# Tone_Level.net
KiCad netlist of a schematic drawn in Altium Designer
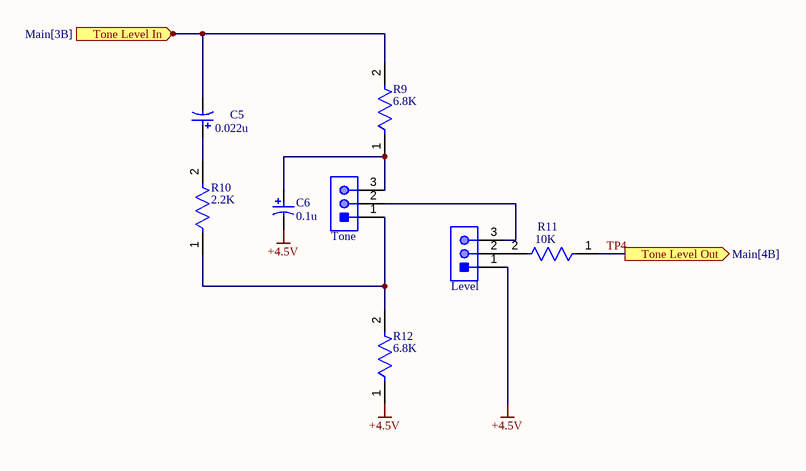
[diagram p0: Tone Level.SchDoc]

(export (version "E")
  (design (tool "Eeschema 10.0.6"))
  (components
    (comp (ref "C5")
      (value "0.022u")
      (footprint "CAPPR55-200-1100X500X1200")
      (description "Aluminum Electrolytic Capacitor, 22 uF, +/- 20%, 50 V, -40 to 85 degC, 2-Pin THD, RoHS, Bulk")
      (fields (field (name "VOLTAGE") "50V") (field (name "MANUFACTURER") "Panasonic"))
      (libsource (lib "Altium Content Vault") (part "CAP-P-2"))
    )
    (comp (ref "C6")
      (value "0.1u")
      (footprint "CAPPR55-200-1100X500X1200")
      (description "Aluminum Electrolytic Capacitor, 22 uF, +/- 20%, 50 V, -40 to 85 degC, 2-Pin THD, RoHS, Bulk")
      (fields (field (name "VOLTAGE") "50V") (field (name "MANUFACTURER") "Panasonic"))
      (libsource (lib "Altium Content Vault") (part "CAP-P-2"))
    )
    (comp (ref "Level")
      (value "100K")
      (footprint "TECO-171825-3_V")
      (fields (field (name "MANUFACTURER") "TE Connectivity"))
      (libsource (lib "Altium Content Vault") (part "CN-1P-M-R3"))
    )
    (comp (ref "R9")
      (value "6.8K")
      (footprint "FP-MRS1600-MFG")
      (description "RES 20K OHM 0.4W 1% AXIAL")
      (fields (field (name "TOLERANCE") "1%"))
      (libsource (lib "Altium Content Vault") (part "1029c3af85768c4190bb7ad29bc67b5"))
    )
    (comp (ref "R10")
      (value "2.2K")
      (footprint "FP-MRS1600-MFG")
      (description "RES 20K OHM 0.4W 1% AXIAL")
      (fields (field (name "TOLERANCE") "1%"))
      (libsource (lib "Altium Content Vault") (part "1029c3af85768c4190bb7ad29bc67b5"))
    )
    (comp (ref "R11")
      (value "10K")
      (footprint "FP-MRS1600-MFG")
      (description "RES 20K OHM 0.4W 1% AXIAL")
      (fields (field (name "TOLERANCE") "1%"))
      (libsource (lib "Altium Content Vault") (part "1029c3af85768c4190bb7ad29bc67b5"))
    )
    (comp (ref "R12")
      (value "6.8K")
      (footprint "FP-MRS1600-MFG")
      (description "RES 20K OHM 0.4W 1% AXIAL")
      (fields (field (name "TOLERANCE") "1%"))
      (libsource (lib "Altium Content Vault") (part "1029c3af85768c4190bb7ad29bc67b5"))
    )
    (comp (ref "Tone")
      (value "20K")
      (footprint "TECO-171825-3_V")
      (fields (field (name "MANUFACTURER") "TE Connectivity"))
      (libsource (lib "Altium Content Vault") (part "CN-1P-M-R3"))
    )
  )
  (nets
    (net (code "1") (name "+4.5V") (class "Default")
      (node (ref "C6") (pin "2") (pinfunction "2_2") (pintype "passive"))
      (node (ref "Level") (pin "1") (pinfunction "1_1") (pintype "passive"))
      (node (ref "R12") (pin "1") (pinfunction "1_1") (pintype "passive"))
    )
    (net (code "2") (name "/TP4") (class "Default")
      (node (ref "R11") (pin "1") (pinfunction "1_1") (pintype "passive"))
    )
    (net (code "3") (name "/Tone Level In") (class "Default")
      (node (ref "C5") (pin "2") (pinfunction "2_2") (pintype "passive"))
      (node (ref "R9") (pin "2") (pinfunction "2_2") (pintype "passive"))
    )
    (net (code "4") (name "Net-(C5-Pad1)") (class "Default")
      (node (ref "C5") (pin "1") (pinfunction "1_1") (pintype "passive"))
      (node (ref "R10") (pin "2") (pinfunction "2_2") (pintype "passive"))
    )
    (net (code "5") (name "Net-(C6-Pad1)") (class "Default")
      (node (ref "C6") (pin "1") (pinfunction "1_1") (pintype "passive"))
      (node (ref "R9") (pin "1") (pinfunction "1_1") (pintype "passive"))
      (node (ref "Tone") (pin "3") (pinfunction "3_3") (pintype "passive"))
    )
    (net (code "6") (name "Net-(Level-Pad2)") (class "Default")
      (node (ref "Level") (pin "2") (pinfunction "2_2") (pintype "passive"))
      (node (ref "R11") (pin "2") (pinfunction "2_2") (pintype "passive"))
    )
    (net (code "7") (name "Net-(Level-Pad3)") (class "Default")
      (node (ref "Level") (pin "3") (pinfunction "3_3") (pintype "passive"))
      (node (ref "Tone") (pin "2") (pinfunction "2_2") (pintype "passive"))
    )
    (net (code "8") (name "Net-(R10-Pad1)") (class "Default")
      (node (ref "R10") (pin "1") (pinfunction "1_1") (pintype "passive"))
      (node (ref "R12") (pin "2") (pinfunction "2_2") (pintype "passive"))
      (node (ref "Tone") (pin "1") (pinfunction "1_1") (pintype "passive"))
    )
  )
)
